# PMOD_IO.net
KiCad netlist of a schematic drawn in Altium Designer
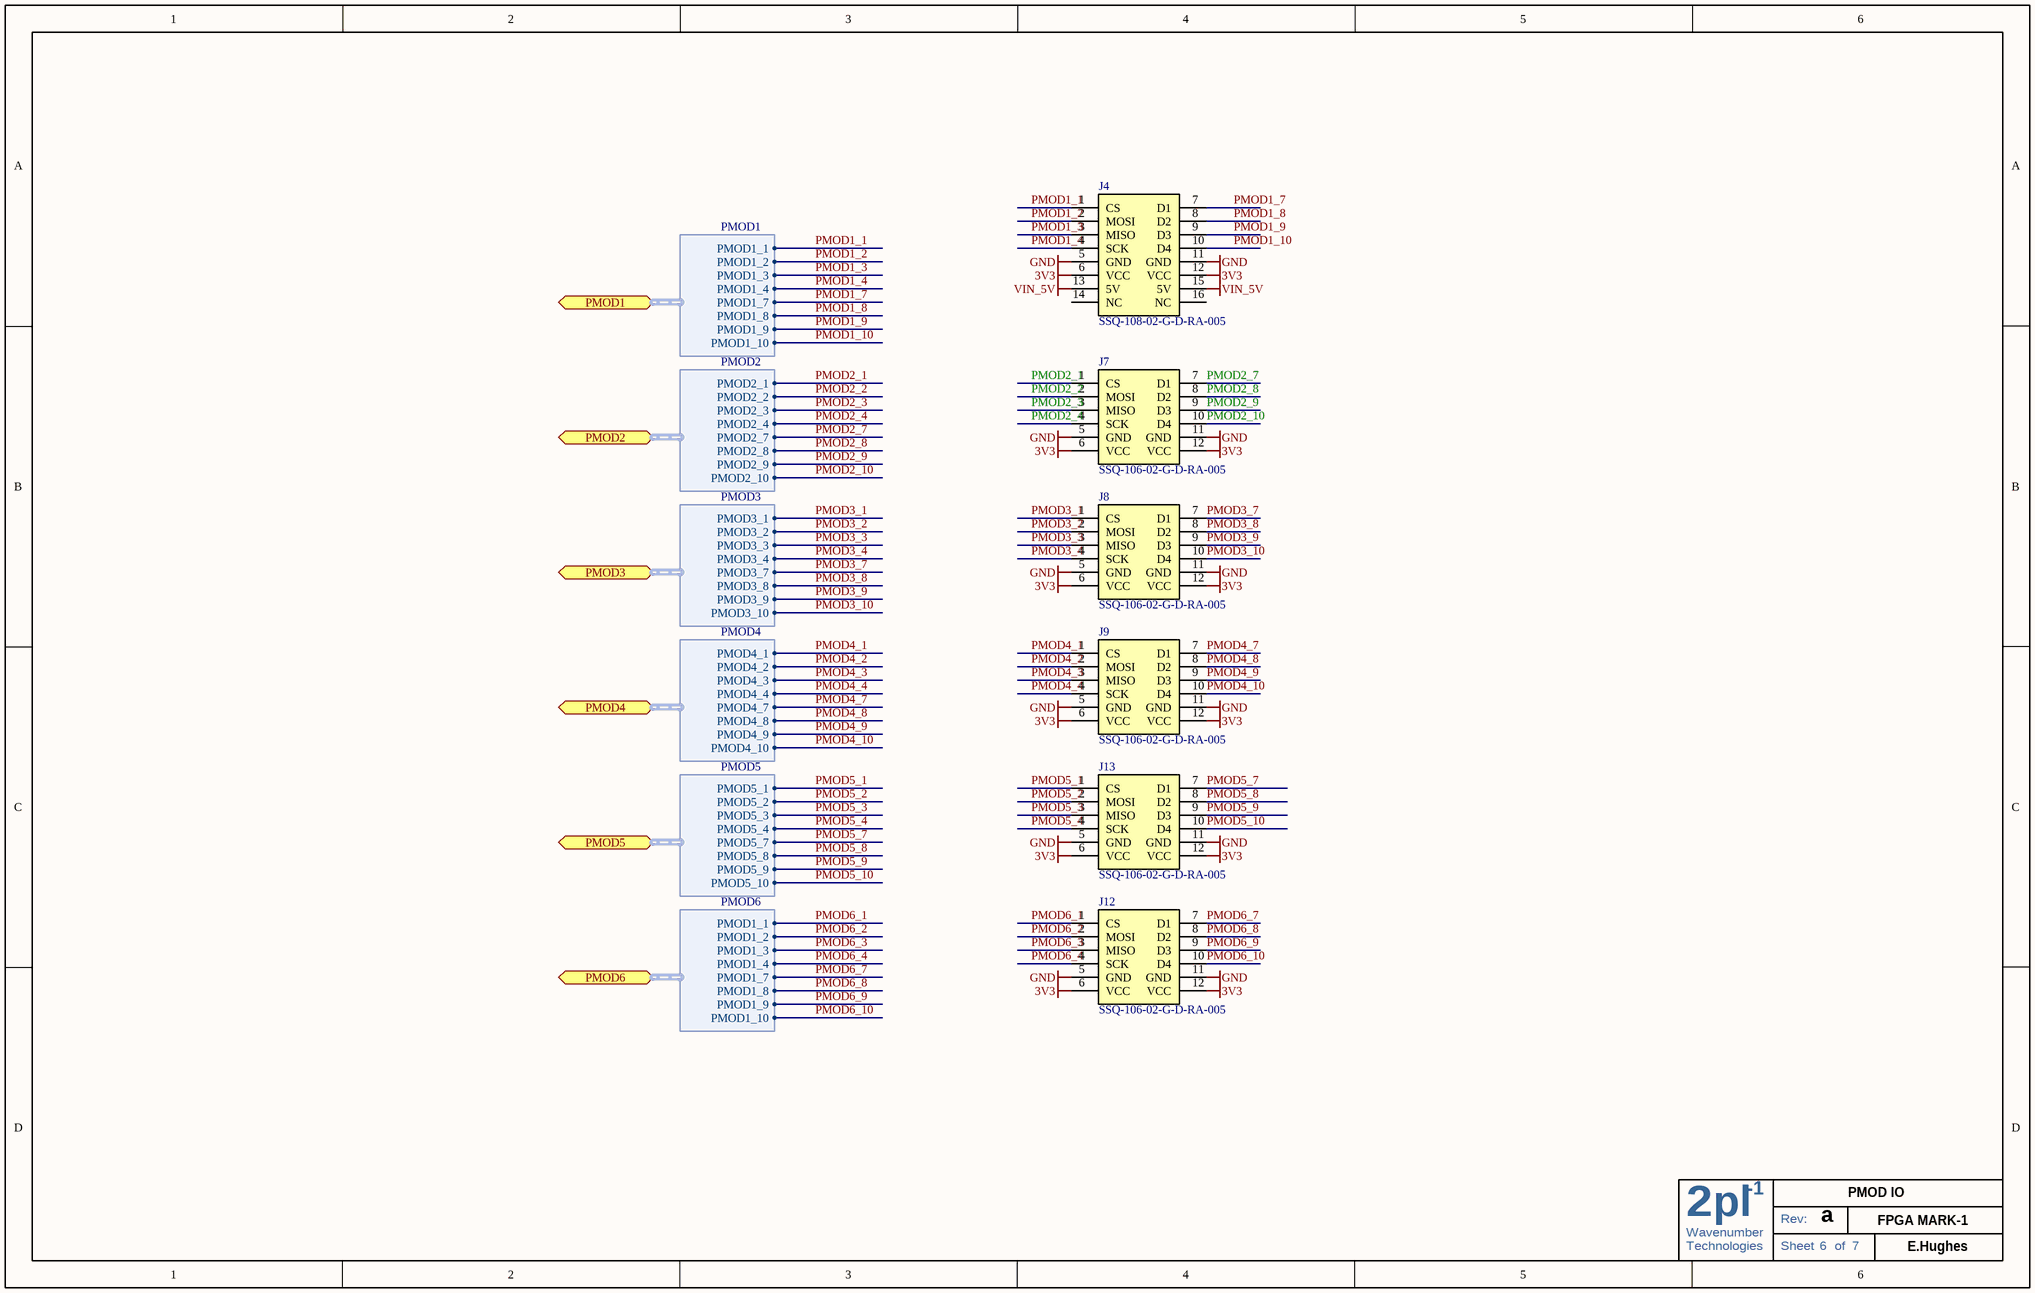
[diagram p0: PMOD_IO.SchDoc]

(export (version "E")
  (design (tool "Eeschema 10.0.6"))
  (components
    (comp (ref "J4")
      (value "SSQ-108-02-G-D-RA-005")
      (footprint "PMOD HEADER8 - SSQ-108-02-G-D-RA")
      (description "SAMTEC - SSQ-108-02-G-D-RA-005 - 2MM SOCKET STRIPS")
      (fields (field (name "MANUFACTURER") "SAMTEC"))
      (libsource (lib "mConnector") (part "P-MOD - SSQ-108-02-G-D-RA-005"))
    )
    (comp (ref "J7")
      (value "SSQ-106-02-G-D-RA-005")
      (footprint "PMOD HEADER - SSQ-106-02-G-D-RA")
      (description "SAMTEC - SSQ-106-02-G-D-RA-005 - 2MM SOCKET STRIPS")
      (fields (field (name "MANUFACTURER") "SAMTEC"))
      (libsource (lib "mConnector") (part "P-MOD - SSQ-106-02-G-D-RA-005"))
    )
    (comp (ref "J8")
      (value "SSQ-106-02-G-D-RA-005")
      (footprint "PMOD HEADER - SSQ-106-02-G-D-RA")
      (description "SAMTEC - SSQ-106-02-G-D-RA-005 - 2MM SOCKET STRIPS")
      (fields (field (name "MANUFACTURER") "SAMTEC"))
      (libsource (lib "mConnector") (part "P-MOD - SSQ-106-02-G-D-RA-005"))
    )
    (comp (ref "J9")
      (value "SSQ-106-02-G-D-RA-005")
      (footprint "PMOD HEADER - SSQ-106-02-G-D-RA")
      (description "SAMTEC - SSQ-106-02-G-D-RA-005 - 2MM SOCKET STRIPS")
      (fields (field (name "MANUFACTURER") "SAMTEC"))
      (libsource (lib "mConnector") (part "P-MOD - SSQ-106-02-G-D-RA-005"))
    )
    (comp (ref "J12")
      (value "SSQ-106-02-G-D-RA-005")
      (footprint "PMOD HEADER - SSQ-106-02-G-D-RA")
      (description "SAMTEC - SSQ-106-02-G-D-RA-005 - 2MM SOCKET STRIPS")
      (fields (field (name "MANUFACTURER") "SAMTEC"))
      (libsource (lib "mConnector") (part "P-MOD - SSQ-106-02-G-D-RA-005"))
    )
    (comp (ref "J13")
      (value "SSQ-106-02-G-D-RA-005")
      (footprint "PMOD HEADER - SSQ-106-02-G-D-RA")
      (description "SAMTEC - SSQ-106-02-G-D-RA-005 - 2MM SOCKET STRIPS")
      (fields (field (name "MANUFACTURER") "SAMTEC"))
      (libsource (lib "mConnector") (part "P-MOD - SSQ-106-02-G-D-RA-005"))
    )
  )
  (nets
    (net (code "7") (name "/PMOD1_1") (class "Default")
      (node (ref "J4") (pin "1") (pinfunction "CS_1") (pintype "power_in"))
    )
    (net (code "8") (name "/PMOD1_2") (class "Default")
      (node (ref "J4") (pin "2") (pinfunction "MOSI_2") (pintype "power_in"))
    )
    (net (code "9") (name "/PMOD1_3") (class "Default")
      (node (ref "J4") (pin "3") (pinfunction "MISO_3") (pintype "power_in"))
    )
    (net (code "10") (name "/PMOD1_4") (class "Default")
      (node (ref "J4") (pin "4") (pinfunction "SCK_4") (pintype "power_in"))
    )
    (net (code "11") (name "/PMOD1_7") (class "Default")
      (node (ref "J4") (pin "7") (pinfunction "D1_7") (pintype "power_in"))
    )
    (net (code "12") (name "/PMOD1_8") (class "Default")
      (node (ref "J4") (pin "8") (pinfunction "D2_8") (pintype "power_in"))
    )
    (net (code "13") (name "/PMOD1_9") (class "Default")
      (node (ref "J4") (pin "9") (pinfunction "D3_9") (pintype "power_in"))
    )
    (net (code "14") (name "/PMOD1_10") (class "Default")
      (node (ref "J4") (pin "10") (pinfunction "D4_10") (pintype "power_in"))
    )
    (net (code "15") (name "/PMOD2_1") (class "Default")
      (node (ref "J7") (pin "1") (pinfunction "CS_1") (pintype "power_in"))
    )
    (net (code "16") (name "/PMOD2_2") (class "Default")
      (node (ref "J7") (pin "2") (pinfunction "MOSI_2") (pintype "power_in"))
    )
    (net (code "17") (name "/PMOD2_3") (class "Default")
      (node (ref "J7") (pin "3") (pinfunction "MISO_3") (pintype "power_in"))
    )
    (net (code "18") (name "/PMOD2_4") (class "Default")
      (node (ref "J7") (pin "4") (pinfunction "SCK_4") (pintype "power_in"))
    )
    (net (code "19") (name "/PMOD2_7") (class "Default")
      (node (ref "J7") (pin "7") (pinfunction "D1_7") (pintype "power_in"))
    )
    (net (code "20") (name "/PMOD2_8") (class "Default")
      (node (ref "J7") (pin "8") (pinfunction "D2_8") (pintype "power_in"))
    )
    (net (code "21") (name "/PMOD2_9") (class "Default")
      (node (ref "J7") (pin "9") (pinfunction "D3_9") (pintype "power_in"))
    )
    (net (code "22") (name "/PMOD2_10") (class "Default")
      (node (ref "J7") (pin "10") (pinfunction "D4_10") (pintype "power_in"))
    )
    (net (code "23") (name "/PMOD3_1") (class "Default")
      (node (ref "J8") (pin "1") (pinfunction "CS_1") (pintype "power_in"))
    )
    (net (code "24") (name "/PMOD3_2") (class "Default")
      (node (ref "J8") (pin "2") (pinfunction "MOSI_2") (pintype "power_in"))
    )
    (net (code "25") (name "/PMOD3_3") (class "Default")
      (node (ref "J8") (pin "3") (pinfunction "MISO_3") (pintype "power_in"))
    )
    (net (code "26") (name "/PMOD3_4") (class "Default")
      (node (ref "J8") (pin "4") (pinfunction "SCK_4") (pintype "power_in"))
    )
    (net (code "27") (name "/PMOD3_7") (class "Default")
      (node (ref "J8") (pin "7") (pinfunction "D1_7") (pintype "power_in"))
    )
    (net (code "28") (name "/PMOD3_8") (class "Default")
      (node (ref "J8") (pin "8") (pinfunction "D2_8") (pintype "power_in"))
    )
    (net (code "29") (name "/PMOD3_9") (class "Default")
      (node (ref "J8") (pin "9") (pinfunction "D3_9") (pintype "power_in"))
    )
    (net (code "30") (name "/PMOD3_10") (class "Default")
      (node (ref "J8") (pin "10") (pinfunction "D4_10") (pintype "power_in"))
    )
    (net (code "31") (name "/PMOD4_1") (class "Default")
      (node (ref "J9") (pin "1") (pinfunction "CS_1") (pintype "power_in"))
    )
    (net (code "32") (name "/PMOD4_2") (class "Default")
      (node (ref "J9") (pin "2") (pinfunction "MOSI_2") (pintype "power_in"))
    )
    (net (code "33") (name "/PMOD4_3") (class "Default")
      (node (ref "J9") (pin "3") (pinfunction "MISO_3") (pintype "power_in"))
    )
    (net (code "34") (name "/PMOD4_4") (class "Default")
      (node (ref "J9") (pin "4") (pinfunction "SCK_4") (pintype "power_in"))
    )
    (net (code "35") (name "/PMOD4_7") (class "Default")
      (node (ref "J9") (pin "7") (pinfunction "D1_7") (pintype "power_in"))
    )
    (net (code "36") (name "/PMOD4_8") (class "Default")
      (node (ref "J9") (pin "8") (pinfunction "D2_8") (pintype "power_in"))
    )
    (net (code "37") (name "/PMOD4_9") (class "Default")
      (node (ref "J9") (pin "9") (pinfunction "D3_9") (pintype "power_in"))
    )
    (net (code "38") (name "/PMOD4_10") (class "Default")
      (node (ref "J9") (pin "10") (pinfunction "D4_10") (pintype "power_in"))
    )
    (net (code "39") (name "/PMOD5_1") (class "Default")
      (node (ref "J13") (pin "1") (pinfunction "CS_1") (pintype "power_in"))
    )
    (net (code "40") (name "/PMOD5_2") (class "Default")
      (node (ref "J13") (pin "2") (pinfunction "MOSI_2") (pintype "power_in"))
    )
    (net (code "41") (name "/PMOD5_3") (class "Default")
      (node (ref "J13") (pin "3") (pinfunction "MISO_3") (pintype "power_in"))
    )
    (net (code "42") (name "/PMOD5_4") (class "Default")
      (node (ref "J13") (pin "4") (pinfunction "SCK_4") (pintype "power_in"))
    )
    (net (code "43") (name "/PMOD5_7") (class "Default")
      (node (ref "J13") (pin "7") (pinfunction "D1_7") (pintype "power_in"))
    )
    (net (code "44") (name "/PMOD5_8") (class "Default")
      (node (ref "J13") (pin "8") (pinfunction "D2_8") (pintype "power_in"))
    )
    (net (code "45") (name "/PMOD5_9") (class "Default")
      (node (ref "J13") (pin "9") (pinfunction "D3_9") (pintype "power_in"))
    )
    (net (code "46") (name "/PMOD5_10") (class "Default")
      (node (ref "J13") (pin "10") (pinfunction "D4_10") (pintype "power_in"))
    )
    (net (code "47") (name "/PMOD6_1") (class "Default")
      (node (ref "J12") (pin "1") (pinfunction "CS_1") (pintype "power_in"))
    )
    (net (code "48") (name "/PMOD6_2") (class "Default")
      (node (ref "J12") (pin "2") (pinfunction "MOSI_2") (pintype "power_in"))
    )
    (net (code "49") (name "/PMOD6_3") (class "Default")
      (node (ref "J12") (pin "3") (pinfunction "MISO_3") (pintype "power_in"))
    )
    (net (code "50") (name "/PMOD6_4") (class "Default")
      (node (ref "J12") (pin "4") (pinfunction "SCK_4") (pintype "power_in"))
    )
    (net (code "51") (name "/PMOD6_7") (class "Default")
      (node (ref "J12") (pin "7") (pinfunction "D1_7") (pintype "power_in"))
    )
    (net (code "52") (name "/PMOD6_8") (class "Default")
      (node (ref "J12") (pin "8") (pinfunction "D2_8") (pintype "power_in"))
    )
    (net (code "53") (name "/PMOD6_9") (class "Default")
      (node (ref "J12") (pin "9") (pinfunction "D3_9") (pintype "power_in"))
    )
    (net (code "54") (name "/PMOD6_10") (class "Default")
      (node (ref "J12") (pin "10") (pinfunction "D4_10") (pintype "power_in"))
    )
    (net (code "61") (name "3V3") (class "Default")
      (node (ref "J12") (pin "12") (pinfunction "VCC_12") (pintype "power_in"))
      (node (ref "J12") (pin "6") (pinfunction "VCC_6") (pintype "power_in"))
      (node (ref "J13") (pin "12") (pinfunction "VCC_12") (pintype "power_in"))
      (node (ref "J13") (pin "6") (pinfunction "VCC_6") (pintype "power_in"))
      (node (ref "J4") (pin "12") (pinfunction "VCC_12") (pintype "power_in"))
      (node (ref "J4") (pin "6") (pinfunction "VCC_6") (pintype "power_in"))
      (node (ref "J7") (pin "12") (pinfunction "VCC_12") (pintype "power_in"))
      (node (ref "J7") (pin "6") (pinfunction "VCC_6") (pintype "power_in"))
      (node (ref "J8") (pin "12") (pinfunction "VCC_12") (pintype "power_in"))
      (node (ref "J8") (pin "6") (pinfunction "VCC_6") (pintype "power_in"))
      (node (ref "J9") (pin "12") (pinfunction "VCC_12") (pintype "power_in"))
      (node (ref "J9") (pin "6") (pinfunction "VCC_6") (pintype "power_in"))
    )
    (net (code "62") (name "GND") (class "Default")
      (node (ref "J12") (pin "11") (pinfunction "GND_11") (pintype "power_in"))
      (node (ref "J12") (pin "5") (pinfunction "GND_5") (pintype "power_in"))
      (node (ref "J13") (pin "11") (pinfunction "GND_11") (pintype "power_in"))
      (node (ref "J13") (pin "5") (pinfunction "GND_5") (pintype "power_in"))
      (node (ref "J4") (pin "11") (pinfunction "GND_11") (pintype "power_in"))
      (node (ref "J4") (pin "5") (pinfunction "GND_5") (pintype "power_in"))
      (node (ref "J7") (pin "11") (pinfunction "GND_11") (pintype "power_in"))
      (node (ref "J7") (pin "5") (pinfunction "GND_5") (pintype "power_in"))
      (node (ref "J8") (pin "11") (pinfunction "GND_11") (pintype "power_in"))
      (node (ref "J8") (pin "5") (pinfunction "GND_5") (pintype "power_in"))
      (node (ref "J9") (pin "11") (pinfunction "GND_11") (pintype "power_in"))
      (node (ref "J9") (pin "5") (pinfunction "GND_5") (pintype "power_in"))
    )
    (net (code "63") (name "VIN_5V") (class "Default")
      (node (ref "J4") (pin "13") (pinfunction "5V_13") (pintype "power_in"))
      (node (ref "J4") (pin "15") (pinfunction "5V_15") (pintype "power_in"))
    )
    (net (code "64") (name "unconnected-(J4-NC-Pad14)") (class "Default")
      (node (ref "J4") (pin "14") (pinfunction "NC_14") (pintype "power_in"))
    )
    (net (code "65") (name "unconnected-(J4-NC-Pad16)") (class "Default")
      (node (ref "J4") (pin "16") (pinfunction "NC_16") (pintype "power_in"))
    )
  )
)
